# OP_Current_Fun-V0_1.net
KiCad netlist of a schematic drawn in EAGLE
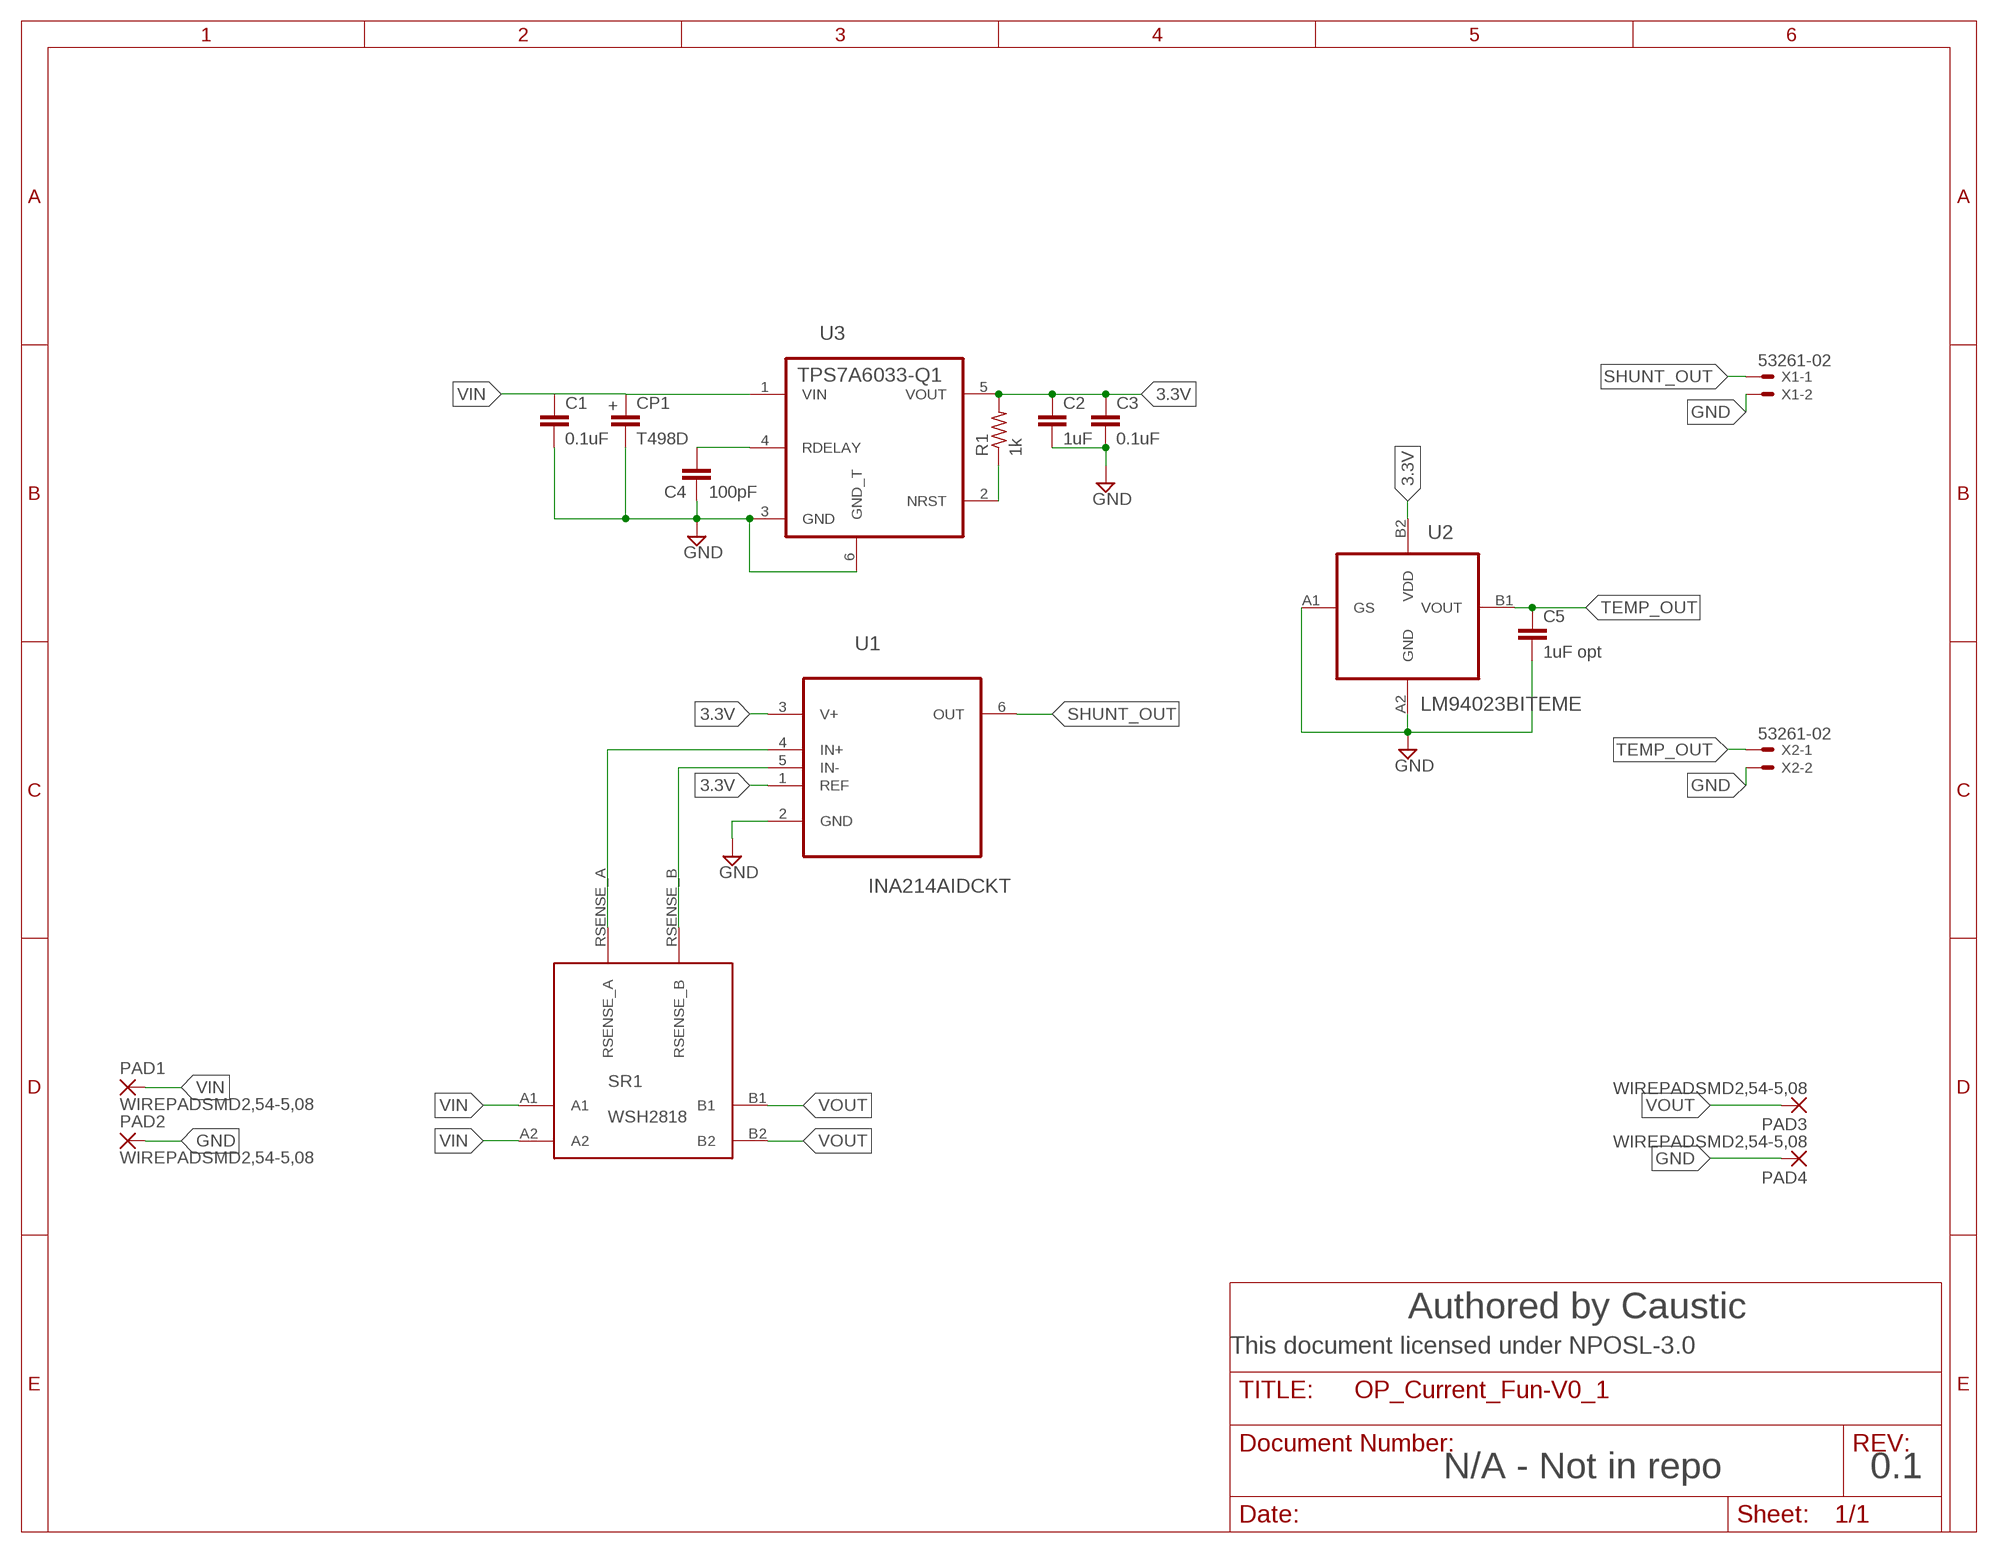
[diagram p0: schematic, sheet 1]

(export (version "E")
  (design (tool "Eeschema 10.0.6"))
  (components
    (comp (ref "C1")
      (value "0.1uF")
      (footprint "eagle-import:C0603K")
      (libsource (lib "eagle-import") (part "C-EUC0603K"))
    )
    (comp (ref "C2")
      (value "1uF")
      (footprint "eagle-import:C0603K")
      (libsource (lib "eagle-import") (part "C-EUC0603K"))
    )
    (comp (ref "C3")
      (value "0.1uF")
      (footprint "eagle-import:C0603K")
      (libsource (lib "eagle-import") (part "C-EUC0603K"))
    )
    (comp (ref "C4")
      (value "100pF")
      (footprint "eagle-import:C0805K")
      (libsource (lib "eagle-import") (part "C-EUC0805K"))
    )
    (comp (ref "C5")
      (value "1uF opt")
      (footprint "eagle-import:C0603K")
      (libsource (lib "eagle-import") (part "C-EUC0603K"))
    )
    (comp (ref "CP1")
      (value "T498D")
      (footprint "eagle-import:CT7343")
      (libsource (lib "eagle-import") (part "T498D"))
    )
    (comp (ref "PAD1")
      (value "WIREPADSMD2,54-5,08")
      (footprint "eagle-import:SMD2,54-5,08")
      (libsource (lib "eagle-import") (part "WIREPADSMD2,54-5,08"))
    )
    (comp (ref "PAD2")
      (value "WIREPADSMD2,54-5,08")
      (footprint "eagle-import:SMD2,54-5,08")
      (libsource (lib "eagle-import") (part "WIREPADSMD2,54-5,08"))
    )
    (comp (ref "PAD3")
      (value "WIREPADSMD2,54-5,08")
      (footprint "eagle-import:SMD2,54-5,08")
      (libsource (lib "eagle-import") (part "WIREPADSMD2,54-5,08"))
    )
    (comp (ref "PAD4")
      (value "WIREPADSMD2,54-5,08")
      (footprint "eagle-import:SMD2,54-5,08")
      (libsource (lib "eagle-import") (part "WIREPADSMD2,54-5,08"))
    )
    (comp (ref "R1")
      (value "1k")
      (footprint "eagle-import:R0402")
      (libsource (lib "eagle-import") (part "R-US_R0402"))
    )
    (comp (ref "SR1")
      (value "WSH2818")
      (footprint "eagle-import:2818")
      (libsource (lib "eagle-import") (part "WSH2818"))
    )
    (comp (ref "U1")
      (value "INA214AIDCKT")
      (footprint "eagle-import:SOT65P210X110-6N")
      (libsource (lib "eagle-import") (part "INA214AIDCKT"))
    )
    (comp (ref "U2")
      (value "LM94023BITEME")
      (footprint "eagle-import:BGA4C40P2X2_76X76X63")
      (libsource (lib "eagle-import") (part "LM94023BITEME"))
    )
    (comp (ref "U3")
      (value "TPS7A6033-Q1")
      (footprint "eagle-import:TO-263-5")
      (libsource (lib "eagle-import") (part "TPS7A6033-Q1"))
    )
    (comp (ref "X1")
      (value "53261-02")
      (footprint "eagle-import:53261-02")
      (libsource (lib "eagle-import") (part "53?-02261"))
    )
    (comp (ref "X2")
      (value "53261-02")
      (footprint "eagle-import:53261-02")
      (libsource (lib "eagle-import") (part "53?-02261"))
    )
  )
  (nets
    (net (code "1") (name "3.3V") (class "Default")
      (node (ref "C2") (pin "1") (pinfunction "1_1") (pintype "passive"))
      (node (ref "C3") (pin "1") (pinfunction "1_1") (pintype "passive"))
      (node (ref "R1") (pin "2") (pinfunction "2_2") (pintype "passive"))
      (node (ref "U1") (pin "1") (pinfunction "REF_1") (pintype "input"))
      (node (ref "U1") (pin "3") (pinfunction "V+_3") (pintype "power_in"))
      (node (ref "U2") (pin "B2") (pinfunction "VDD_B2") (pintype "power_in"))
      (node (ref "U3") (pin "5") (pinfunction "VOUT_5") (pintype "output"))
    )
    (net (code "2") (name "GND") (class "Default")
      (node (ref "C1") (pin "2") (pinfunction "2_2") (pintype "passive"))
      (node (ref "C2") (pin "2") (pinfunction "2_2") (pintype "passive"))
      (node (ref "C3") (pin "2") (pinfunction "2_2") (pintype "passive"))
      (node (ref "C4") (pin "1") (pinfunction "1_1") (pintype "passive"))
      (node (ref "C5") (pin "2") (pinfunction "2_2") (pintype "passive"))
      (node (ref "CP1") (pin "-") (pinfunction "2_-") (pintype "passive"))
      (node (ref "PAD2") (pin "1") (pinfunction "P_1") (pintype "passive"))
      (node (ref "PAD4") (pin "1") (pinfunction "P_1") (pintype "passive"))
      (node (ref "U1") (pin "2") (pinfunction "GND_2") (pintype "passive"))
      (node (ref "U2") (pin "A1") (pinfunction "GS_A1") (pintype "input"))
      (node (ref "U2") (pin "A2") (pinfunction "GND_A2") (pintype "passive"))
      (node (ref "U3") (pin "3") (pinfunction "GND_3") (pintype "passive"))
      (node (ref "U3") (pin "6") (pinfunction "GND_T_6") (pintype "passive"))
      (node (ref "X1") (pin "2") (pinfunction "S_2") (pintype "passive"))
      (node (ref "X2") (pin "2") (pinfunction "S_2") (pintype "passive"))
    )
    (net (code "3") (name "Net-(U1-IN+)") (class "Default")
      (node (ref "SR1") (pin "RSENSE_A") (pinfunction "RSENSE_A_RSENSE_A") (pintype "passive"))
      (node (ref "U1") (pin "4") (pinfunction "IN+_4") (pintype "input"))
    )
    (net (code "4") (name "Net-(U1-IN-)") (class "Default")
      (node (ref "SR1") (pin "RSENSE_B") (pinfunction "RSENSE_B_RSENSE_B") (pintype "passive"))
      (node (ref "U1") (pin "5") (pinfunction "IN-_5") (pintype "input"))
    )
    (net (code "5") (name "Net-(U3-NRST)") (class "Default")
      (node (ref "R1") (pin "1") (pinfunction "1_1") (pintype "passive"))
      (node (ref "U3") (pin "2") (pinfunction "NRST_2") (pintype "output"))
    )
    (net (code "6") (name "Net-(U3-RDELAY)") (class "Default")
      (node (ref "C4") (pin "2") (pinfunction "2_2") (pintype "passive"))
      (node (ref "U3") (pin "4") (pinfunction "RDELAY_4") (pintype "output"))
    )
    (net (code "7") (name "SHUNT_OUT") (class "Default")
      (node (ref "U1") (pin "6") (pinfunction "OUT_6") (pintype "output"))
      (node (ref "X1") (pin "1") (pinfunction "S_1") (pintype "passive"))
    )
    (net (code "8") (name "TEMP_OUT") (class "Default")
      (node (ref "C5") (pin "1") (pinfunction "1_1") (pintype "passive"))
      (node (ref "U2") (pin "B1") (pinfunction "VOUT_B1") (pintype "output"))
      (node (ref "X2") (pin "1") (pinfunction "S_1") (pintype "passive"))
    )
    (net (code "9") (name "VIN") (class "Default")
      (node (ref "C1") (pin "1") (pinfunction "1_1") (pintype "passive"))
      (node (ref "CP1") (pin "+") (pinfunction "1_+") (pintype "passive"))
      (node (ref "PAD1") (pin "1") (pinfunction "P_1") (pintype "passive"))
      (node (ref "SR1") (pin "A1") (pinfunction "A1_A1") (pintype "passive"))
      (node (ref "SR1") (pin "A2") (pinfunction "A2_A2") (pintype "passive"))
      (node (ref "U3") (pin "1") (pinfunction "VIN_1") (pintype "power_in"))
    )
    (net (code "10") (name "VOUT") (class "Default")
      (node (ref "PAD3") (pin "1") (pinfunction "P_1") (pintype "passive"))
      (node (ref "SR1") (pin "B1") (pinfunction "B1_B1") (pintype "passive"))
      (node (ref "SR1") (pin "B2") (pinfunction "B2_B2") (pintype "passive"))
    )
  )
)
